# pressure.net
KiCad netlist of a schematic drawn in EAGLE
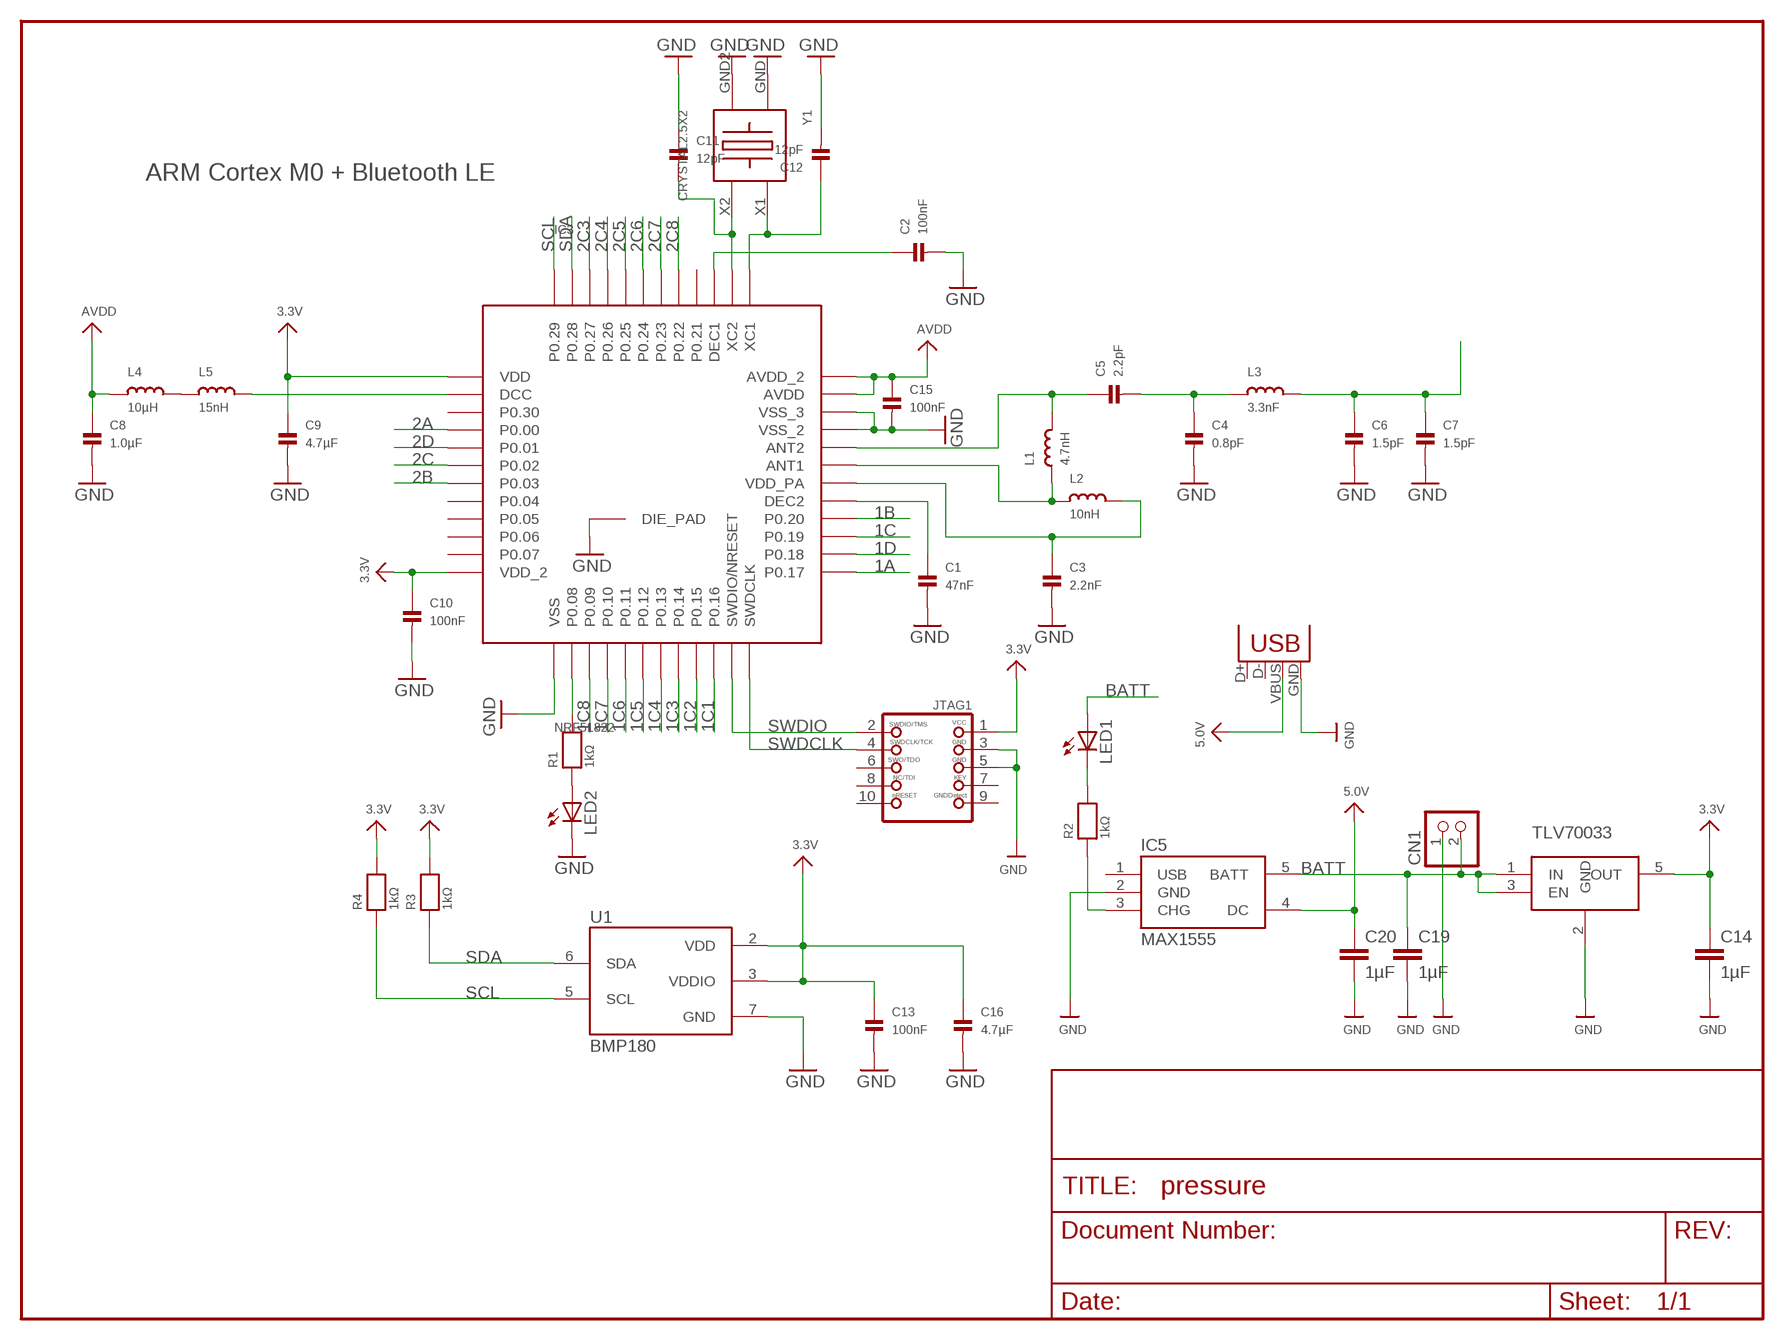
[diagram p0: schematic, sheet 1]

(export (version "E")
  (design (tool "Eeschema 10.0.6"))
  (components
    (comp (ref "C1")
      (value "47nF")
      (footprint "eagle-import:_0402")
      (libsource (lib "eagle-import") (part "CAP_CERAMIC_0402"))
    )
    (comp (ref "C2")
      (value "100nF")
      (footprint "eagle-import:_0402")
      (libsource (lib "eagle-import") (part "CAP_CERAMIC_0402"))
    )
    (comp (ref "C3")
      (value "2.2nF")
      (footprint "eagle-import:_0402")
      (libsource (lib "eagle-import") (part "CAP_CERAMIC_0402"))
    )
    (comp (ref "C4")
      (value "0.8pF")
      (footprint "eagle-import:_0402")
      (libsource (lib "eagle-import") (part "CAP_CERAMIC_0402"))
    )
    (comp (ref "C5")
      (value "2.2pF")
      (footprint "eagle-import:_0402")
      (libsource (lib "eagle-import") (part "CAP_CERAMIC_0402"))
    )
    (comp (ref "C6")
      (value "1.5pF")
      (footprint "eagle-import:_0402")
      (libsource (lib "eagle-import") (part "CAP_CERAMIC_0402"))
    )
    (comp (ref "C7")
      (value "1.5pF")
      (footprint "eagle-import:_0402")
      (libsource (lib "eagle-import") (part "CAP_CERAMIC_0402"))
    )
    (comp (ref "C8")
      (value "1.0µF")
      (footprint "eagle-import:_0402")
      (libsource (lib "eagle-import") (part "CAP_CERAMIC_0402"))
    )
    (comp (ref "C9")
      (value "4.7µF")
      (footprint "eagle-import:_0402")
      (libsource (lib "eagle-import") (part "CAP_CERAMIC_0402"))
    )
    (comp (ref "C10")
      (value "100nF")
      (footprint "eagle-import:_0402")
      (libsource (lib "eagle-import") (part "CAP_CERAMIC_0402"))
    )
    (comp (ref "C11")
      (value "12pF")
      (footprint "eagle-import:_0402")
      (libsource (lib "eagle-import") (part "CAP_CERAMIC_0402"))
    )
    (comp (ref "C12")
      (value "12pF")
      (footprint "eagle-import:_0402")
      (libsource (lib "eagle-import") (part "CAP_CERAMIC_0402"))
    )
    (comp (ref "C13")
      (value "100nF")
      (footprint "eagle-import:_0402")
      (libsource (lib "eagle-import") (part "CAP_CERAMIC_0402"))
    )
    (comp (ref "C14")
      (value "1µF")
      (footprint "eagle-import:C0603K")
      (libsource (lib "eagle-import") (part "C-EUC0603K"))
    )
    (comp (ref "C15")
      (value "100nF")
      (footprint "eagle-import:_0402")
      (libsource (lib "eagle-import") (part "CAP_CERAMIC_0402"))
    )
    (comp (ref "C16")
      (value "4.7µF")
      (footprint "eagle-import:_0402")
      (libsource (lib "eagle-import") (part "CAP_CERAMIC_0402"))
    )
    (comp (ref "C19")
      (value "1µF")
      (footprint "eagle-import:C0603K")
      (libsource (lib "eagle-import") (part "C-EUC0603K"))
    )
    (comp (ref "C20")
      (value "1µF")
      (footprint "eagle-import:C0603K")
      (libsource (lib "eagle-import") (part "C-EUC0603K"))
    )
    (comp (ref "CN1")
      (value "JST_2PIN")
      (footprint "eagle-import:JSTPH2")
      (libsource (lib "eagle-import") (part "JST_2PIN"))
    )
    (comp (ref "IC3")
      (value "NRF51822")
      (footprint "eagle-import:QFN48")
      (libsource (lib "eagle-import") (part "NRF51822"))
    )
    (comp (ref "IC4")
      (value "TLV70033DCK")
      (footprint "eagle-import:SC70-5L")
      (libsource (lib "eagle-import") (part "TLV700DCK"))
    )
    (comp (ref "IC5")
      (value "MAX1555")
      (footprint "eagle-import:SOT23-5")
      (libsource (lib "eagle-import") (part "MAX1555"))
    )
    (comp (ref "JTAG1")
      (value "JTAG-CORTEXM3SMT")
      (footprint "eagle-import:2X05_1.27MM_SMT")
      (libsource (lib "eagle-import") (part "JTAG-CORTEXM3SMT"))
    )
    (comp (ref "L1")
      (value "4.7nH")
      (footprint "eagle-import:_0402")
      (libsource (lib "eagle-import") (part "INDUCTOR_0402"))
    )
    (comp (ref "L2")
      (value "10nH")
      (footprint "eagle-import:_0402")
      (libsource (lib "eagle-import") (part "INDUCTOR_0402"))
    )
    (comp (ref "L3")
      (value "3.3nF")
      (footprint "eagle-import:_0402")
      (libsource (lib "eagle-import") (part "INDUCTOR_0402"))
    )
    (comp (ref "L4")
      (value "10µH")
      (footprint "eagle-import:_0402")
      (libsource (lib "eagle-import") (part "INDUCTOR_0402"))
    )
    (comp (ref "L5")
      (value "15nH")
      (footprint "eagle-import:_0402")
      (libsource (lib "eagle-import") (part "INDUCTOR_0402"))
    )
    (comp (ref "LED1")
      (value "LEDCHIPLED_0603")
      (footprint "eagle-import:CHIPLED_0603")
      (libsource (lib "eagle-import") (part "LEDCHIPLED_0603"))
    )
    (comp (ref "LED2")
      (value "LEDCHIPLED_0603")
      (footprint "eagle-import:CHIPLED_0603")
      (libsource (lib "eagle-import") (part "LEDCHIPLED_0603"))
    )
    (comp (ref "R1")
      (value "1kΩ")
      (footprint "eagle-import:_0402")
      (libsource (lib "eagle-import") (part "RESISTOR_0402"))
    )
    (comp (ref "R2")
      (value "1kΩ")
      (footprint "eagle-import:_0402")
      (libsource (lib "eagle-import") (part "RESISTOR_0402"))
    )
    (comp (ref "R3")
      (value "1kΩ")
      (footprint "eagle-import:_0402")
      (libsource (lib "eagle-import") (part "RESISTOR_0402"))
    )
    (comp (ref "R4")
      (value "1kΩ")
      (footprint "eagle-import:_0402")
      (libsource (lib "eagle-import") (part "RESISTOR_0402"))
    )
    (comp (ref "U1")
      (value "BMP180")
      (footprint "eagle-import:BMP180")
      (libsource (lib "eagle-import") (part "BMP180"))
    )
    (comp (ref "X1")
      (value "USB-MICROB")
      (footprint "eagle-import:USB-MICROB")
      (libsource (lib "eagle-import") (part "USB-MICROB"))
    )
    (comp (ref "Y1")
      (value "CRYSTAL2.5X2")
      (footprint "eagle-import:2.5X2MM")
      (libsource (lib "eagle-import") (part "CRYSTAL2.5X2"))
    )
  )
  (nets
    (net (code "1") (name "/1A") (class "Default")
      (node (ref "IC3") (pin "25") (pinfunction "P0.17_25") (pintype "bidirectional"))
    )
    (net (code "2") (name "/1B") (class "Default")
      (node (ref "IC3") (pin "28") (pinfunction "P0.20_28") (pintype "bidirectional"))
    )
    (net (code "3") (name "/1C") (class "Default")
      (node (ref "IC3") (pin "27") (pinfunction "P0.19_27") (pintype "bidirectional"))
    )
    (net (code "4") (name "/1C1") (class "Default")
      (node (ref "IC3") (pin "22") (pinfunction "P0.16_22") (pintype "bidirectional"))
    )
    (net (code "5") (name "/1C2") (class "Default")
      (node (ref "IC3") (pin "21") (pinfunction "P0.15_21") (pintype "bidirectional"))
    )
    (net (code "6") (name "/1C3") (class "Default")
      (node (ref "IC3") (pin "20") (pinfunction "P0.14_20") (pintype "bidirectional"))
    )
    (net (code "7") (name "/1C4") (class "Default")
      (node (ref "IC3") (pin "19") (pinfunction "P0.13_19") (pintype "bidirectional"))
    )
    (net (code "8") (name "/1C5") (class "Default")
      (node (ref "IC3") (pin "18") (pinfunction "P0.12_18") (pintype "bidirectional"))
    )
    (net (code "9") (name "/1C6") (class "Default")
      (node (ref "IC3") (pin "17") (pinfunction "P0.11_17") (pintype "bidirectional"))
    )
    (net (code "10") (name "/1C7") (class "Default")
      (node (ref "IC3") (pin "16") (pinfunction "P0.10_16") (pintype "bidirectional"))
    )
    (net (code "11") (name "/1C8") (class "Default")
      (node (ref "IC3") (pin "15") (pinfunction "P0.09_15") (pintype "bidirectional"))
    )
    (net (code "12") (name "/1D") (class "Default")
      (node (ref "IC3") (pin "26") (pinfunction "P0.18_26") (pintype "bidirectional"))
    )
    (net (code "13") (name "/2A") (class "Default")
      (node (ref "IC3") (pin "4") (pinfunction "P0.00_4") (pintype "bidirectional"))
    )
    (net (code "14") (name "/2B") (class "Default")
      (node (ref "IC3") (pin "7") (pinfunction "P0.03_7") (pintype "bidirectional"))
    )
    (net (code "15") (name "/2C") (class "Default")
      (node (ref "IC3") (pin "6") (pinfunction "P0.02_6") (pintype "bidirectional"))
    )
    (net (code "16") (name "/2C3") (class "Default")
      (node (ref "IC3") (pin "46") (pinfunction "P0.27_46") (pintype "bidirectional"))
    )
    (net (code "17") (name "/2C4") (class "Default")
      (node (ref "IC3") (pin "45") (pinfunction "P0.26_45") (pintype "bidirectional"))
    )
    (net (code "18") (name "/2C5") (class "Default")
      (node (ref "IC3") (pin "44") (pinfunction "P0.25_44") (pintype "bidirectional"))
    )
    (net (code "19") (name "/2C6") (class "Default")
      (node (ref "IC3") (pin "43") (pinfunction "P0.24_43") (pintype "bidirectional"))
    )
    (net (code "20") (name "/2C7") (class "Default")
      (node (ref "IC3") (pin "42") (pinfunction "P0.23_42") (pintype "bidirectional"))
    )
    (net (code "21") (name "/2C8") (class "Default")
      (node (ref "IC3") (pin "41") (pinfunction "P0.22_41") (pintype "bidirectional"))
    )
    (net (code "22") (name "/2D") (class "Default")
      (node (ref "IC3") (pin "5") (pinfunction "P0.01_5") (pintype "bidirectional"))
    )
    (net (code "23") (name "/BATT") (class "Default")
      (node (ref "C19") (pin "1") (pinfunction "1_1") (pintype "passive"))
      (node (ref "CN1") (pin "2") (pinfunction "2_2") (pintype "passive"))
      (node (ref "IC4") (pin "1") (pinfunction "IN_1") (pintype "bidirectional"))
      (node (ref "IC4") (pin "3") (pinfunction "EN_3") (pintype "bidirectional"))
      (node (ref "IC5") (pin "5") (pinfunction "BATT_5") (pintype "bidirectional"))
      (node (ref "LED1") (pin "A") (pinfunction "A_A") (pintype "passive"))
    )
    (net (code "24") (name "/SCL") (class "Default")
      (node (ref "IC3") (pin "48") (pinfunction "P0.29_48") (pintype "bidirectional"))
      (node (ref "R4") (pin "1") (pinfunction "1_1") (pintype "passive"))
      (node (ref "U1") (pin "5") (pinfunction "SCL_5") (pintype "input"))
    )
    (net (code "25") (name "/SDA") (class "Default")
      (node (ref "IC3") (pin "47") (pinfunction "P0.28_47") (pintype "bidirectional"))
      (node (ref "R3") (pin "1") (pinfunction "1_1") (pintype "passive"))
      (node (ref "U1") (pin "6") (pinfunction "SDA_6") (pintype "bidirectional"))
    )
    (net (code "26") (name "/SWDCLK") (class "Default")
      (node (ref "IC3") (pin "24") (pinfunction "SWDCLK_24") (pintype "bidirectional"))
      (node (ref "JTAG1") (pin "4") (pinfunction "4_4") (pintype "passive"))
    )
    (net (code "27") (name "/SWDIO") (class "Default")
      (node (ref "IC3") (pin "23") (pinfunction "SWDIO/NRESET_23") (pintype "bidirectional"))
      (node (ref "JTAG1") (pin "2") (pinfunction "2_2") (pintype "passive"))
    )
    (net (code "28") (name "3.3V") (class "Default")
      (node (ref "C10") (pin "1") (pinfunction "P$1_1") (pintype "passive"))
      (node (ref "C13") (pin "1") (pinfunction "P$1_1") (pintype "passive"))
      (node (ref "C14") (pin "1") (pinfunction "1_1") (pintype "passive"))
      (node (ref "C16") (pin "1") (pinfunction "P$1_1") (pintype "passive"))
      (node (ref "C9") (pin "1") (pinfunction "P$1_1") (pintype "passive"))
      (node (ref "IC3") (pin "1") (pinfunction "VDD_1") (pintype "bidirectional"))
      (node (ref "IC3") (pin "12") (pinfunction "VDD_2_12") (pintype "bidirectional"))
      (node (ref "IC4") (pin "5") (pinfunction "OUT_5") (pintype "bidirectional"))
      (node (ref "JTAG1") (pin "1") (pinfunction "1_1") (pintype "passive"))
      (node (ref "R3") (pin "2") (pinfunction "2_2") (pintype "passive"))
      (node (ref "R4") (pin "2") (pinfunction "2_2") (pintype "passive"))
      (node (ref "U1") (pin "2") (pinfunction "VDD_2") (pintype "power_in"))
      (node (ref "U1") (pin "3") (pinfunction "VDDIO_3") (pintype "power_in"))
    )
    (net (code "29") (name "5.0V") (class "Default")
      (node (ref "C20") (pin "1") (pinfunction "1_1") (pintype "passive"))
      (node (ref "IC5") (pin "4") (pinfunction "DC_4") (pintype "bidirectional"))
      (node (ref "X1") (pin "VBUS") (pinfunction "VBUS_VBUS") (pintype "bidirectional"))
    )
    (net (code "30") (name "AVDD") (class "Default")
      (node (ref "C15") (pin "1") (pinfunction "P$1_1") (pintype "passive"))
      (node (ref "C8") (pin "1") (pinfunction "P$1_1") (pintype "passive"))
      (node (ref "IC3") (pin "35") (pinfunction "AVDD_35") (pintype "bidirectional"))
      (node (ref "IC3") (pin "36") (pinfunction "AVDD_2_36") (pintype "bidirectional"))
      (node (ref "L4") (pin "1") (pinfunction "1_1") (pintype "passive"))
    )
    (net (code "31") (name "GND") (class "Default")
      (node (ref "C1") (pin "2") (pinfunction "P$2_2") (pintype "passive"))
      (node (ref "C10") (pin "2") (pinfunction "P$2_2") (pintype "passive"))
      (node (ref "C11") (pin "1") (pinfunction "P$1_1") (pintype "passive"))
      (node (ref "C12") (pin "2") (pinfunction "P$2_2") (pintype "passive"))
      (node (ref "C13") (pin "2") (pinfunction "P$2_2") (pintype "passive"))
      (node (ref "C14") (pin "2") (pinfunction "2_2") (pintype "passive"))
      (node (ref "C15") (pin "2") (pinfunction "P$2_2") (pintype "passive"))
      (node (ref "C16") (pin "2") (pinfunction "P$2_2") (pintype "passive"))
      (node (ref "C19") (pin "2") (pinfunction "2_2") (pintype "passive"))
      (node (ref "C2") (pin "2") (pinfunction "P$2_2") (pintype "passive"))
      (node (ref "C20") (pin "2") (pinfunction "2_2") (pintype "passive"))
      (node (ref "C3") (pin "2") (pinfunction "P$2_2") (pintype "passive"))
      (node (ref "C4") (pin "2") (pinfunction "P$2_2") (pintype "passive"))
      (node (ref "C6") (pin "2") (pinfunction "P$2_2") (pintype "passive"))
      (node (ref "C7") (pin "2") (pinfunction "P$2_2") (pintype "passive"))
      (node (ref "C8") (pin "2") (pinfunction "P$2_2") (pintype "passive"))
      (node (ref "C9") (pin "2") (pinfunction "P$2_2") (pintype "passive"))
      (node (ref "CN1") (pin "1") (pinfunction "1_1") (pintype "passive"))
      (node (ref "IC3") (pin "13") (pinfunction "VSS_13") (pintype "bidirectional"))
      (node (ref "IC3") (pin "33") (pinfunction "VSS_2_33") (pintype "bidirectional"))
      (node (ref "IC3") (pin "34") (pinfunction "VSS_3_34") (pintype "bidirectional"))
      (node (ref "IC3") (pin "GND") (pinfunction "DIE_PAD_GND") (pintype "bidirectional"))
      (node (ref "IC4") (pin "2") (pinfunction "GND_2") (pintype "bidirectional"))
      (node (ref "IC5") (pin "2") (pinfunction "GND_2") (pintype "bidirectional"))
      (node (ref "JTAG1") (pin "3") (pinfunction "3_3") (pintype "passive"))
      (node (ref "JTAG1") (pin "5") (pinfunction "5_5") (pintype "passive"))
      (node (ref "LED2") (pin "C") (pinfunction "C_C") (pintype "passive"))
      (node (ref "U1") (pin "7") (pinfunction "GND_7") (pintype "power_in"))
      (node (ref "X1") (pin "GND") (pinfunction "GND_GND") (pintype "bidirectional"))
      (node (ref "Y1") (pin "GND") (pinfunction "GND_GND") (pintype "bidirectional"))
      (node (ref "Y1") (pin "GND2") (pinfunction "GND2_GND2") (pintype "bidirectional"))
    )
    (net (code "32") (name "Net-(C1-P$1)") (class "Default")
      (node (ref "C1") (pin "1") (pinfunction "P$1_1") (pintype "passive"))
      (node (ref "IC3") (pin "29") (pinfunction "DEC2_29") (pintype "bidirectional"))
    )
    (net (code "33") (name "Net-(C2-P$1)") (class "Default")
      (node (ref "C2") (pin "1") (pinfunction "P$1_1") (pintype "passive"))
      (node (ref "IC3") (pin "39") (pinfunction "DEC1_39") (pintype "bidirectional"))
    )
    (net (code "34") (name "Net-(C3-P$1)") (class "Default")
      (node (ref "C3") (pin "1") (pinfunction "P$1_1") (pintype "passive"))
      (node (ref "IC3") (pin "30") (pinfunction "VDD_PA_30") (pintype "bidirectional"))
      (node (ref "L2") (pin "2") (pinfunction "2_2") (pintype "passive"))
    )
    (net (code "35") (name "Net-(C4-P$1)") (class "Default")
      (node (ref "C4") (pin "1") (pinfunction "P$1_1") (pintype "passive"))
      (node (ref "C5") (pin "2") (pinfunction "P$2_2") (pintype "passive"))
      (node (ref "L3") (pin "1") (pinfunction "1_1") (pintype "passive"))
    )
    (net (code "36") (name "Net-(C5-P$1)") (class "Default")
      (node (ref "C5") (pin "1") (pinfunction "P$1_1") (pintype "passive"))
      (node (ref "IC3") (pin "32") (pinfunction "ANT2_32") (pintype "bidirectional"))
      (node (ref "L1") (pin "2") (pinfunction "2_2") (pintype "passive"))
    )
    (net (code "37") (name "Net-(C6-P$1)") (class "Default")
      (node (ref "C6") (pin "1") (pinfunction "P$1_1") (pintype "passive"))
      (node (ref "C7") (pin "1") (pinfunction "P$1_1") (pintype "passive"))
      (node (ref "L3") (pin "2") (pinfunction "2_2") (pintype "passive"))
    )
    (net (code "38") (name "Net-(C11-P$2)") (class "Default")
      (node (ref "C11") (pin "2") (pinfunction "P$2_2") (pintype "passive"))
      (node (ref "IC3") (pin "38") (pinfunction "XC2_38") (pintype "bidirectional"))
      (node (ref "Y1") (pin "X2") (pinfunction "X2_X2") (pintype "bidirectional"))
    )
    (net (code "39") (name "Net-(C12-P$1)") (class "Default")
      (node (ref "C12") (pin "1") (pinfunction "P$1_1") (pintype "passive"))
      (node (ref "IC3") (pin "37") (pinfunction "XC1_37") (pintype "bidirectional"))
      (node (ref "Y1") (pin "X1") (pinfunction "X1_X1") (pintype "bidirectional"))
    )
    (net (code "40") (name "Net-(IC3-ANT1)") (class "Default")
      (node (ref "IC3") (pin "31") (pinfunction "ANT1_31") (pintype "bidirectional"))
      (node (ref "L1") (pin "1") (pinfunction "1_1") (pintype "passive"))
      (node (ref "L2") (pin "1") (pinfunction "1_1") (pintype "passive"))
    )
    (net (code "41") (name "Net-(IC3-DCC)") (class "Default")
      (node (ref "IC3") (pin "2") (pinfunction "DCC_2") (pintype "bidirectional"))
      (node (ref "L5") (pin "2") (pinfunction "2_2") (pintype "passive"))
    )
    (net (code "42") (name "Net-(IC3-P0.08)") (class "Default")
      (node (ref "IC3") (pin "14") (pinfunction "P0.08_14") (pintype "bidirectional"))
      (node (ref "R1") (pin "2") (pinfunction "2_2") (pintype "passive"))
    )
    (net (code "43") (name "Net-(IC5-CHG)") (class "Default")
      (node (ref "IC5") (pin "3") (pinfunction "CHG_3") (pintype "bidirectional"))
      (node (ref "R2") (pin "1") (pinfunction "1_1") (pintype "passive"))
    )
    (net (code "44") (name "Net-(L4-Pad2)") (class "Default")
      (node (ref "L4") (pin "2") (pinfunction "2_2") (pintype "passive"))
      (node (ref "L5") (pin "1") (pinfunction "1_1") (pintype "passive"))
    )
    (net (code "45") (name "Net-(LED1-PadC)") (class "Default")
      (node (ref "LED1") (pin "C") (pinfunction "C_C") (pintype "passive"))
      (node (ref "R2") (pin "2") (pinfunction "2_2") (pintype "passive"))
    )
    (net (code "46") (name "Net-(LED2-PadA)") (class "Default")
      (node (ref "LED2") (pin "A") (pinfunction "A_A") (pintype "passive"))
      (node (ref "R1") (pin "1") (pinfunction "1_1") (pintype "passive"))
    )
    (net (code "47") (name "unconnected-(IC3-P0.04-Pad8)") (class "Default")
      (node (ref "IC3") (pin "8") (pinfunction "P0.04_8") (pintype "bidirectional"))
    )
    (net (code "48") (name "unconnected-(IC3-P0.05-Pad9)") (class "Default")
      (node (ref "IC3") (pin "9") (pinfunction "P0.05_9") (pintype "bidirectional"))
    )
    (net (code "49") (name "unconnected-(IC3-P0.06-Pad10)") (class "Default")
      (node (ref "IC3") (pin "10") (pinfunction "P0.06_10") (pintype "bidirectional"))
    )
    (net (code "50") (name "unconnected-(IC3-P0.07-Pad11)") (class "Default")
      (node (ref "IC3") (pin "11") (pinfunction "P0.07_11") (pintype "bidirectional"))
    )
    (net (code "51") (name "unconnected-(IC3-P0.21-Pad40)") (class "Default")
      (node (ref "IC3") (pin "40") (pinfunction "P0.21_40") (pintype "bidirectional"))
    )
    (net (code "52") (name "unconnected-(IC3-P0.30-Pad3)") (class "Default")
      (node (ref "IC3") (pin "3") (pinfunction "P0.30_3") (pintype "bidirectional"))
    )
    (net (code "53") (name "unconnected-(IC5-USB-Pad1)") (class "Default")
      (node (ref "IC5") (pin "1") (pinfunction "USB_1") (pintype "bidirectional"))
    )
    (net (code "54") (name "unconnected-(JTAG1-Pad6)") (class "Default")
      (node (ref "JTAG1") (pin "6") (pinfunction "6_6") (pintype "passive"))
    )
    (net (code "55") (name "unconnected-(JTAG1-Pad7)") (class "Default")
      (node (ref "JTAG1") (pin "7") (pinfunction "7_7") (pintype "passive"))
    )
    (net (code "56") (name "unconnected-(JTAG1-Pad8)") (class "Default")
      (node (ref "JTAG1") (pin "8") (pinfunction "8_8") (pintype "passive"))
    )
    (net (code "57") (name "unconnected-(JTAG1-Pad9)") (class "Default")
      (node (ref "JTAG1") (pin "9") (pinfunction "9_9") (pintype "passive"))
    )
    (net (code "58") (name "unconnected-(JTAG1-Pad10)") (class "Default")
      (node (ref "JTAG1") (pin "10") (pinfunction "10_10") (pintype "passive"))
    )
    (net (code "59") (name "unconnected-(X1-PadD+)") (class "Default")
      (node (ref "X1") (pin "D+") (pinfunction "D+_D+") (pintype "bidirectional"))
    )
    (net (code "60") (name "unconnected-(X1-PadD-)") (class "Default")
      (node (ref "X1") (pin "D-") (pinfunction "D-_D-") (pintype "bidirectional"))
    )
  )
)
